# Grove_-_Mini_Track_ball_v1_0.net
KiCad netlist of a schematic drawn in EAGLE
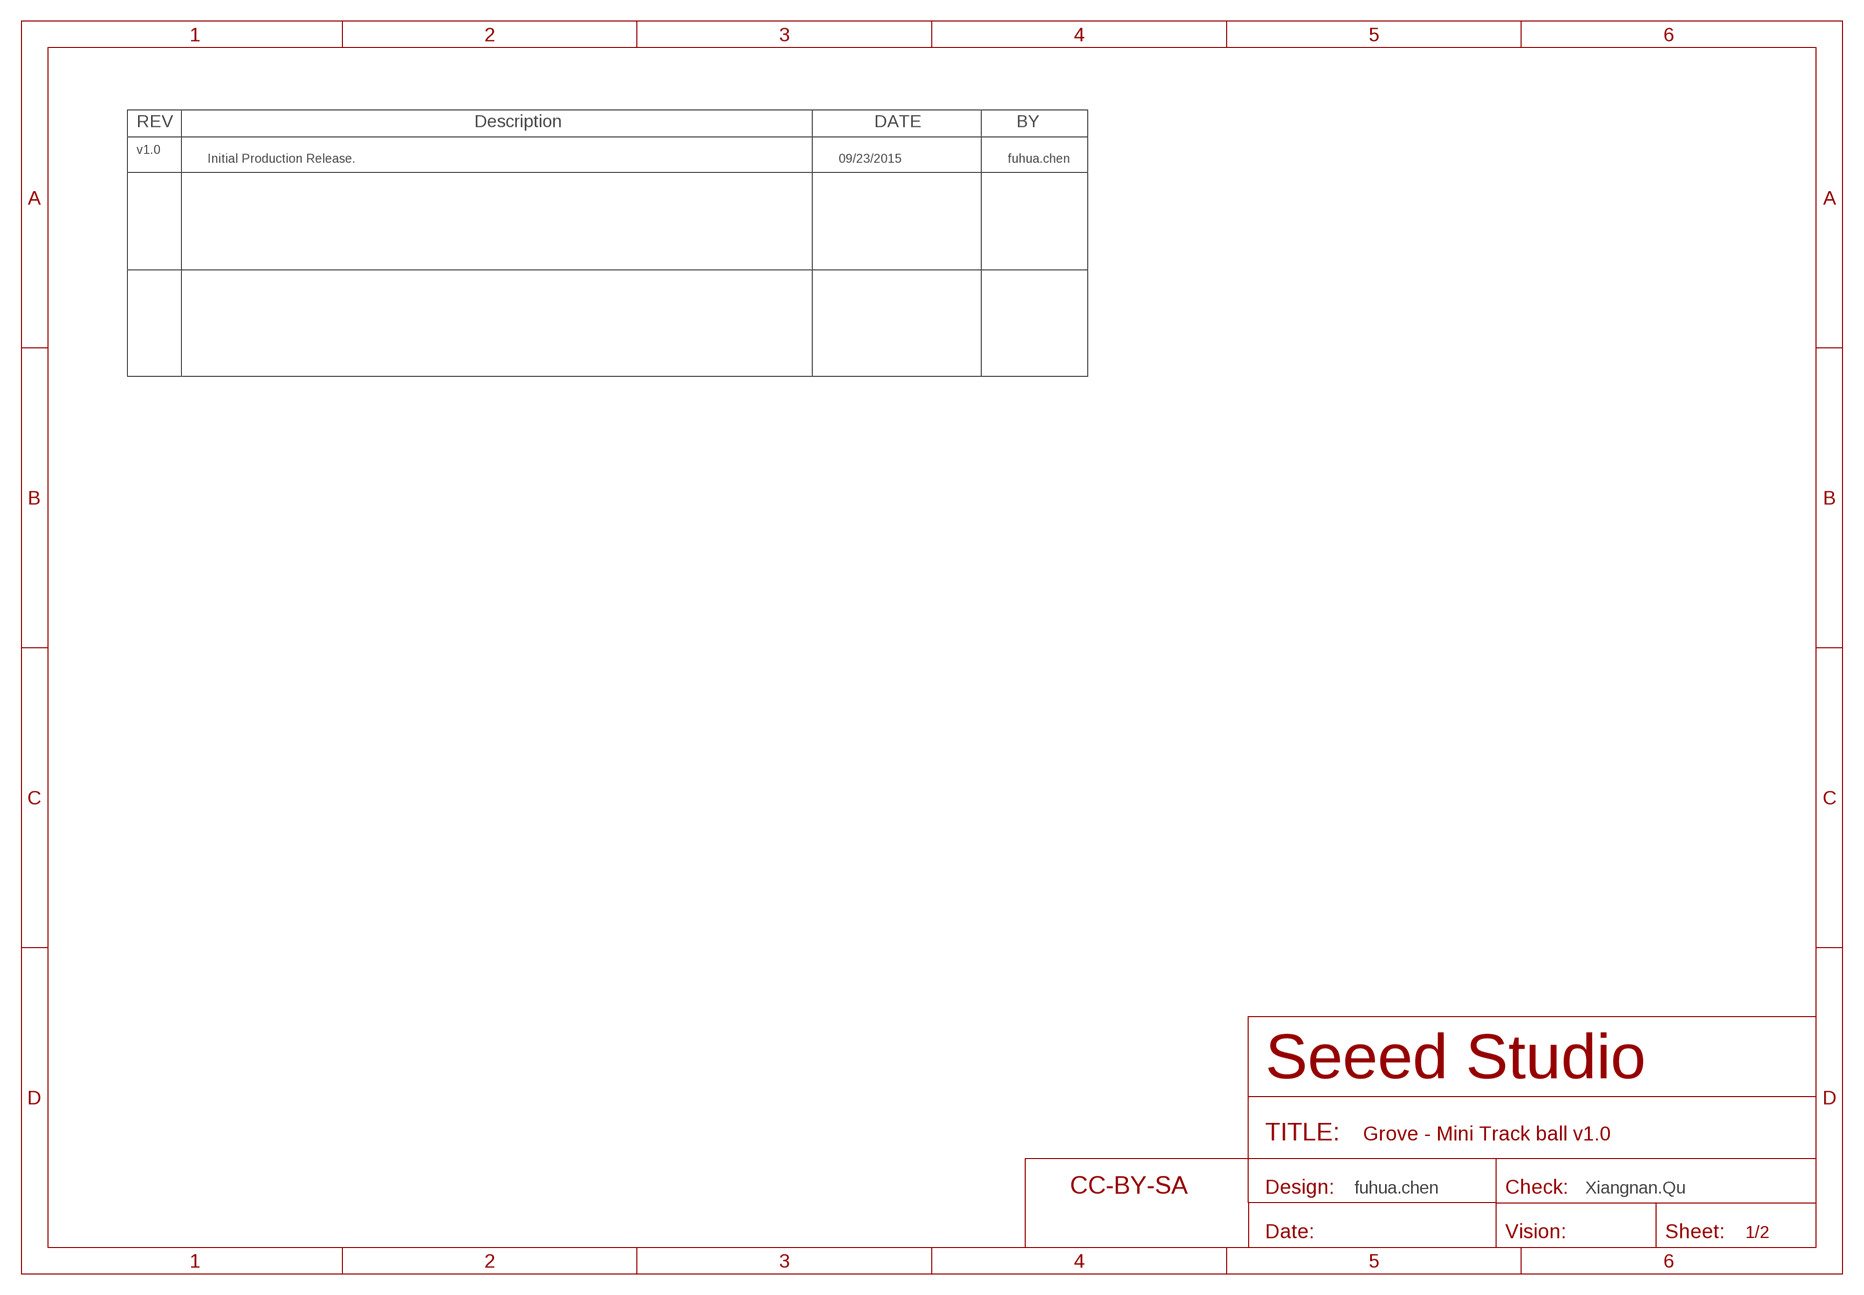
[diagram p0: schematic, sheet 1]
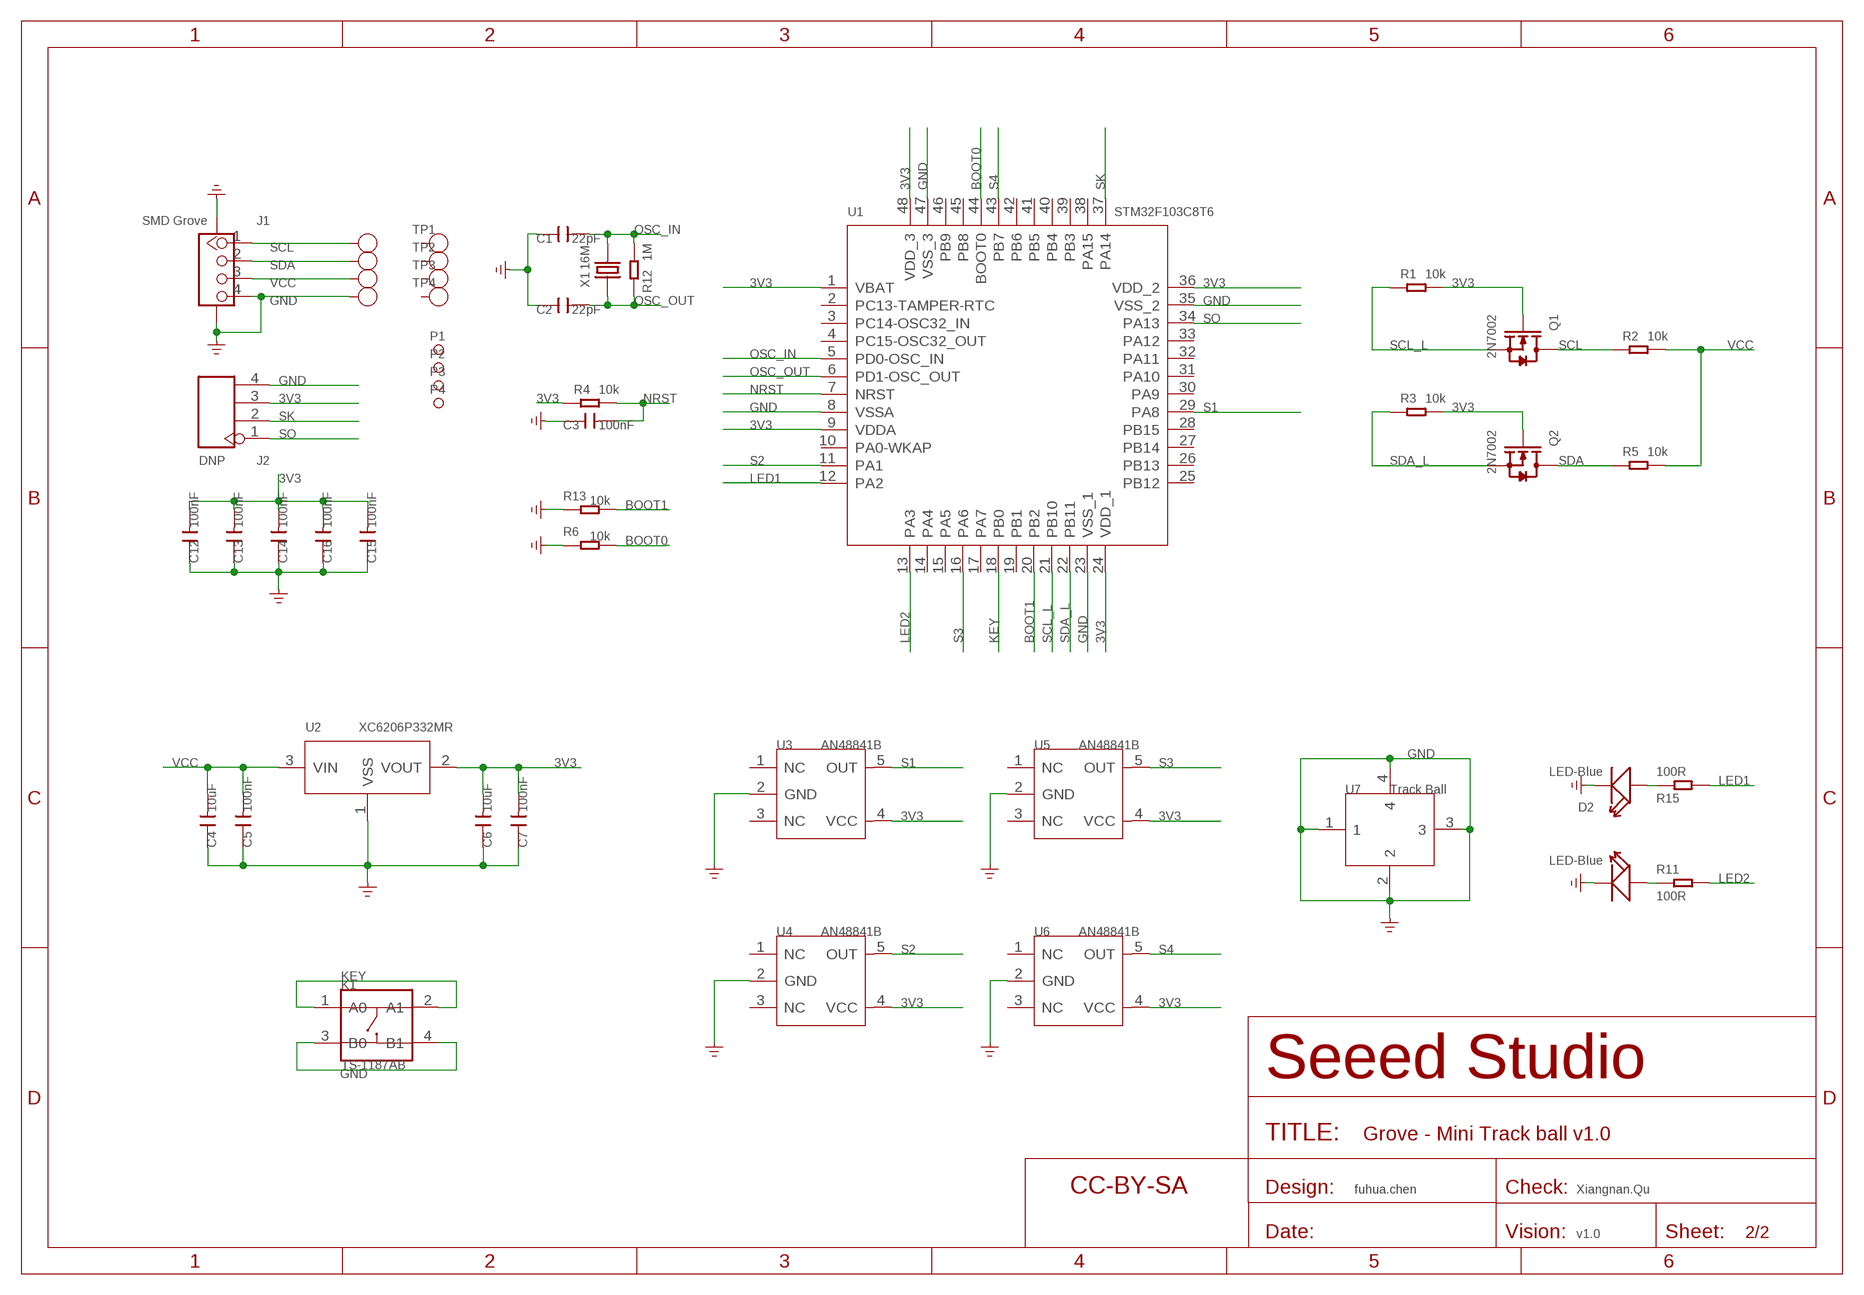
[diagram p1: schematic, sheet 2]

(export (version "E")
  (design (tool "Eeschema 10.0.6"))
  (components
    (comp (ref "C1")
      (value "22pF")
      (footprint "eagle-import:C0402")
      (libsource (lib "eagle-import") (part "CAP-0402"))
    )
    (comp (ref "C2")
      (value "22pF")
      (footprint "eagle-import:C0402")
      (libsource (lib "eagle-import") (part "CAP-0402"))
    )
    (comp (ref "C3")
      (value "100nF")
      (footprint "eagle-import:C0402")
      (libsource (lib "eagle-import") (part "CAP-0402"))
    )
    (comp (ref "C4")
      (value "10uF")
      (footprint "eagle-import:C0402")
      (libsource (lib "eagle-import") (part "CAP-0402"))
    )
    (comp (ref "C5")
      (value "100nF")
      (footprint "eagle-import:C0402")
      (libsource (lib "eagle-import") (part "CAP-0402"))
    )
    (comp (ref "C6")
      (value "10uF")
      (footprint "eagle-import:C0402")
      (libsource (lib "eagle-import") (part "CAP-0402"))
    )
    (comp (ref "C7")
      (value "100nF")
      (footprint "eagle-import:C0402")
      (libsource (lib "eagle-import") (part "CAP-0402"))
    )
    (comp (ref "C12")
      (value "100nF")
      (footprint "eagle-import:C0402")
      (libsource (lib "eagle-import") (part "CAP-0402"))
    )
    (comp (ref "C13")
      (value "100nF")
      (footprint "eagle-import:C0402")
      (libsource (lib "eagle-import") (part "CAP-0402"))
    )
    (comp (ref "C14")
      (value "100nF")
      (footprint "eagle-import:C0402")
      (libsource (lib "eagle-import") (part "CAP-0402"))
    )
    (comp (ref "C15")
      (value "100nF")
      (footprint "eagle-import:C0402")
      (libsource (lib "eagle-import") (part "CAP-0402"))
    )
    (comp (ref "C16")
      (value "100nF")
      (footprint "eagle-import:C0402")
      (libsource (lib "eagle-import") (part "CAP-0402"))
    )
    (comp (ref "D1")
      (value "LED-Blue")
      (footprint "eagle-import:LED-0402")
      (libsource (lib "eagle-import") (part "LED'0402'"))
    )
    (comp (ref "D2")
      (value "LED-Blue")
      (footprint "eagle-import:LED-0402")
      (libsource (lib "eagle-import") (part "LED'0402'"))
    )
    (comp (ref "FR")
      (value "SEEEDSTUDIO-OPEN-SCH-FRAME")
      (footprint "eagle-import:SEEEDSTUDIO-PCB-FRAME")
      (libsource (lib "eagle-import") (part "SEEEDSTUDIO-OPEN-SCH-FRAME"))
    )
    (comp (ref "GND")
      (value "GND")
      (footprint "eagle-import:TP-D45MIL")
      (fields (field (name "PARTNO") "DNP"))
      (libsource (lib "eagle-import") (part "TEST-POINT'4545'"))
    )
    (comp (ref "J1")
      (value "SMD Grove")
      (footprint "eagle-import:HW4-SMD-2.0-90D")
      (libsource (lib "eagle-import") (part "GROVE-CONNECTOR-SMD'90D'"))
    )
    (comp (ref "J2")
      (value "DNP")
      (footprint "eagle-import:H4-2.54")
      (libsource (lib "eagle-import") (part "HEADER-4P-65/35MIL"))
    )
    (comp (ref "K1")
      (value "TS-1187AB")
      (footprint "eagle-import:SW4-4.5X4.5X0.5MM")
      (libsource (lib "eagle-import") (part "BUTTON-4P-4.5X4.5"))
    )
    (comp (ref "P1")
      (value "MARK-1.0'ANNULAR'")
      (footprint "eagle-import:ROUND-MARK-1.0")
      (fields (field (name "PARTNO") "DNP"))
      (libsource (lib "eagle-import") (part "MARK-1.0'ANNULAR'"))
    )
    (comp (ref "P2")
      (value "MARK-1.0'ANNULAR'")
      (footprint "eagle-import:ROUND-MARK-1.0")
      (fields (field (name "PARTNO") "DNP"))
      (libsource (lib "eagle-import") (part "MARK-1.0'ANNULAR'"))
    )
    (comp (ref "P3")
      (value "MARK-1.0'ANNULAR'")
      (footprint "eagle-import:ROUND-MARK-1.0")
      (fields (field (name "PARTNO") "DNP"))
      (libsource (lib "eagle-import") (part "MARK-1.0'ANNULAR'"))
    )
    (comp (ref "P4")
      (value "MARK-1.0'ANNULAR'")
      (footprint "eagle-import:ROUND-MARK-1.0")
      (fields (field (name "PARTNO") "DNP"))
      (libsource (lib "eagle-import") (part "MARK-1.0'ANNULAR'"))
    )
    (comp (ref "Q1")
      (value "2N7002")
      (footprint "eagle-import:SOT-23")
      (libsource (lib "eagle-import") (part "MOSFET-N'SOT23'"))
    )
    (comp (ref "Q2")
      (value "2N7002")
      (footprint "eagle-import:SOT-23")
      (libsource (lib "eagle-import") (part "MOSFET-N'SOT23'"))
    )
    (comp (ref "R1")
      (value "10k")
      (footprint "eagle-import:R0402")
      (libsource (lib "eagle-import") (part "RES-0402"))
    )
    (comp (ref "R2")
      (value "10k")
      (footprint "eagle-import:R0402")
      (libsource (lib "eagle-import") (part "RES-0402"))
    )
    (comp (ref "R3")
      (value "10k")
      (footprint "eagle-import:R0402")
      (libsource (lib "eagle-import") (part "RES-0402"))
    )
    (comp (ref "R4")
      (value "10k")
      (footprint "eagle-import:R0402")
      (libsource (lib "eagle-import") (part "RES-0402"))
    )
    (comp (ref "R5")
      (value "10k")
      (footprint "eagle-import:R0402")
      (libsource (lib "eagle-import") (part "RES-0402"))
    )
    (comp (ref "R6")
      (value "10k")
      (footprint "eagle-import:R0402")
      (libsource (lib "eagle-import") (part "RES-0402"))
    )
    (comp (ref "R11")
      (value "100R")
      (footprint "eagle-import:R0402")
      (libsource (lib "eagle-import") (part "RES-0402"))
    )
    (comp (ref "R12")
      (value "1M")
      (footprint "eagle-import:R0402")
      (libsource (lib "eagle-import") (part "RES-0402"))
    )
    (comp (ref "R13")
      (value "10k")
      (footprint "eagle-import:R0402")
      (libsource (lib "eagle-import") (part "RES-0402"))
    )
    (comp (ref "R15")
      (value "100R")
      (footprint "eagle-import:R0402")
      (libsource (lib "eagle-import") (part "RES-0402"))
    )
    (comp (ref "SCL")
      (value "SCL")
      (footprint "eagle-import:TP-D45MIL")
      (fields (field (name "PARTNO") "DNP"))
      (libsource (lib "eagle-import") (part "TEST-POINT'4545'"))
    )
    (comp (ref "SDA")
      (value "SDA")
      (footprint "eagle-import:TP-D45MIL")
      (fields (field (name "PARTNO") "DNP"))
      (libsource (lib "eagle-import") (part "TEST-POINT'4545'"))
    )
    (comp (ref "TP1")
      (value "TEST-POINT'4545'")
      (footprint "eagle-import:TP-D45MIL")
      (fields (field (name "PARTNO") "DNP"))
      (libsource (lib "eagle-import") (part "TEST-POINT'4545'"))
    )
    (comp (ref "TP2")
      (value "TEST-POINT'4545'")
      (footprint "eagle-import:TP-D45MIL")
      (fields (field (name "PARTNO") "DNP"))
      (libsource (lib "eagle-import") (part "TEST-POINT'4545'"))
    )
    (comp (ref "TP3")
      (value "TEST-POINT'4545'")
      (footprint "eagle-import:TP-D45MIL")
      (fields (field (name "PARTNO") "DNP"))
      (libsource (lib "eagle-import") (part "TEST-POINT'4545'"))
    )
    (comp (ref "TP4")
      (value "TEST-POINT'4545'")
      (footprint "eagle-import:TP-D45MIL")
      (fields (field (name "PARTNO") "DNP"))
      (libsource (lib "eagle-import") (part "TEST-POINT'4545'"))
    )
    (comp (ref "U1")
      (value "STM32F103C8T6")
      (footprint "eagle-import:LQFP48")
      (libsource (lib "eagle-import") (part "MCU-STM32F103CBT6"))
    )
    (comp (ref "U2")
      (value "XC6206P332MR")
      (footprint "eagle-import:SOT-23")
      (libsource (lib "eagle-import") (part "PMIC-XC6206PMR"))
    )
    (comp (ref "U3")
      (value "AN48841B")
      (footprint "eagle-import:SMINI-5DE")
      (libsource (lib "eagle-import") (part "SENSOR-AN48841B"))
    )
    (comp (ref "U4")
      (value "AN48841B")
      (footprint "eagle-import:SMINI-5DE")
      (libsource (lib "eagle-import") (part "SENSOR-AN48841B"))
    )
    (comp (ref "U5")
      (value "AN48841B")
      (footprint "eagle-import:SMINI-5DE")
      (libsource (lib "eagle-import") (part "SENSOR-AN48841B"))
    )
    (comp (ref "U6")
      (value "AN48841B")
      (footprint "eagle-import:SMINI-5DE")
      (libsource (lib "eagle-import") (part "SENSOR-AN48841B"))
    )
    (comp (ref "U7")
      (value "Track Ball")
      (footprint "eagle-import:BALL4P-9.1X9.1X6.04MM")
      (libsource (lib "eagle-import") (part "TRACK-BALL"))
    )
    (comp (ref "VCC")
      (value "VCC")
      (footprint "eagle-import:TP-D45MIL")
      (fields (field (name "PARTNO") "DNP"))
      (libsource (lib "eagle-import") (part "TEST-POINT'4545'"))
    )
    (comp (ref "X1")
      (value "16M")
      (footprint "eagle-import:X4-SMD-3.2X2.5X0.7MM")
      (libsource (lib "eagle-import") (part "CRYSTAL-2P'3225'"))
    )
    (comp (ref "U$13")
      (value "SEEEDSTUDIO-OPEN-SCH-FRAME")
      (footprint "eagle-import:SEEEDSTUDIO-PCB-FRAME")
      (libsource (lib "eagle-import") (part "SEEEDSTUDIO-OPEN-SCH-FRAME"))
    )
  )
  (nets
    (net (code "1") (name "3V3") (class "Default")
      (node (ref "C12") (pin "2") (pinfunction "2_2") (pintype "passive"))
      (node (ref "C13") (pin "2") (pinfunction "2_2") (pintype "passive"))
      (node (ref "C14") (pin "2") (pinfunction "2_2") (pintype "passive"))
      (node (ref "C15") (pin "2") (pinfunction "2_2") (pintype "passive"))
      (node (ref "C16") (pin "2") (pinfunction "2_2") (pintype "passive"))
      (node (ref "C6") (pin "2") (pinfunction "2_2") (pintype "passive"))
      (node (ref "C7") (pin "2") (pinfunction "2_2") (pintype "passive"))
      (node (ref "J2") (pin "3") (pinfunction "P$3_3") (pintype "bidirectional"))
      (node (ref "Q1") (pin "1") (pinfunction "G_1") (pintype "passive"))
      (node (ref "Q2") (pin "1") (pinfunction "G_1") (pintype "passive"))
      (node (ref "R1") (pin "2") (pinfunction "2_2") (pintype "passive"))
      (node (ref "R3") (pin "2") (pinfunction "2_2") (pintype "passive"))
      (node (ref "R4") (pin "1") (pinfunction "1_1") (pintype "passive"))
      (node (ref "U1") (pin "1") (pinfunction "VBAT_1") (pintype "bidirectional"))
      (node (ref "U1") (pin "24") (pinfunction "VDD_1_24") (pintype "bidirectional"))
      (node (ref "U1") (pin "36") (pinfunction "VDD_2_36") (pintype "bidirectional"))
      (node (ref "U1") (pin "48") (pinfunction "VDD_3_48") (pintype "bidirectional"))
      (node (ref "U1") (pin "9") (pinfunction "VDDA_9") (pintype "bidirectional"))
      (node (ref "U2") (pin "2") (pinfunction "VOUT_2") (pintype "bidirectional"))
      (node (ref "U3") (pin "4") (pinfunction "VCC_4") (pintype "bidirectional"))
      (node (ref "U4") (pin "4") (pinfunction "VCC_4") (pintype "bidirectional"))
      (node (ref "U5") (pin "4") (pinfunction "VCC_4") (pintype "bidirectional"))
      (node (ref "U6") (pin "4") (pinfunction "VCC_4") (pintype "bidirectional"))
    )
    (net (code "2") (name "BOOT0") (class "Default")
      (node (ref "R6") (pin "2") (pinfunction "2_2") (pintype "passive"))
      (node (ref "U1") (pin "44") (pinfunction "BOOT0_44") (pintype "bidirectional"))
    )
    (net (code "3") (name "BOOT1") (class "Default")
      (node (ref "R13") (pin "2") (pinfunction "2_2") (pintype "passive"))
      (node (ref "U1") (pin "20") (pinfunction "PB2_20") (pintype "bidirectional"))
    )
    (net (code "4") (name "GND") (class "Default")
      (node (ref "C1") (pin "1") (pinfunction "1_1") (pintype "passive"))
      (node (ref "C12") (pin "1") (pinfunction "1_1") (pintype "passive"))
      (node (ref "C13") (pin "1") (pinfunction "1_1") (pintype "passive"))
      (node (ref "C14") (pin "1") (pinfunction "1_1") (pintype "passive"))
      (node (ref "C15") (pin "1") (pinfunction "1_1") (pintype "passive"))
      (node (ref "C16") (pin "1") (pinfunction "1_1") (pintype "passive"))
      (node (ref "C2") (pin "1") (pinfunction "1_1") (pintype "passive"))
      (node (ref "C3") (pin "1") (pinfunction "1_1") (pintype "passive"))
      (node (ref "C4") (pin "1") (pinfunction "1_1") (pintype "passive"))
      (node (ref "C5") (pin "1") (pinfunction "1_1") (pintype "passive"))
      (node (ref "C6") (pin "1") (pinfunction "1_1") (pintype "passive"))
      (node (ref "C7") (pin "1") (pinfunction "1_1") (pintype "passive"))
      (node (ref "D1") (pin "-") (pinfunction "-_-") (pintype "passive"))
      (node (ref "D2") (pin "-") (pinfunction "-_-") (pintype "passive"))
      (node (ref "GND") (pin "T") (pinfunction "T_T") (pintype "bidirectional"))
      (node (ref "J1") (pin "4") (pinfunction "4_4") (pintype "bidirectional"))
      (node (ref "J1") (pin "SS1") (pinfunction "SS1_SS1") (pintype "bidirectional"))
      (node (ref "J1") (pin "SS2") (pinfunction "SS2_SS2") (pintype "bidirectional"))
      (node (ref "J2") (pin "4") (pinfunction "P$4_4") (pintype "bidirectional"))
      (node (ref "K1") (pin "3") (pinfunction "B0_3") (pintype "bidirectional"))
      (node (ref "K1") (pin "4") (pinfunction "B1_4") (pintype "bidirectional"))
      (node (ref "R13") (pin "1") (pinfunction "1_1") (pintype "passive"))
      (node (ref "R6") (pin "1") (pinfunction "1_1") (pintype "passive"))
      (node (ref "U1") (pin "23") (pinfunction "VSS_1_23") (pintype "bidirectional"))
      (node (ref "U1") (pin "35") (pinfunction "VSS_2_35") (pintype "bidirectional"))
      (node (ref "U1") (pin "47") (pinfunction "VSS_3_47") (pintype "bidirectional"))
      (node (ref "U1") (pin "8") (pinfunction "VSSA_8") (pintype "bidirectional"))
      (node (ref "U2") (pin "1") (pinfunction "VSS_1") (pintype "bidirectional"))
      (node (ref "U3") (pin "2") (pinfunction "GND_2") (pintype "bidirectional"))
      (node (ref "U4") (pin "2") (pinfunction "GND_2") (pintype "bidirectional"))
      (node (ref "U5") (pin "2") (pinfunction "GND_2") (pintype "bidirectional"))
      (node (ref "U6") (pin "2") (pinfunction "GND_2") (pintype "bidirectional"))
      (node (ref "U7") (pin "1") (pinfunction "1_1") (pintype "bidirectional"))
      (node (ref "U7") (pin "2") (pinfunction "2_2") (pintype "bidirectional"))
      (node (ref "U7") (pin "3") (pinfunction "3_3") (pintype "bidirectional"))
      (node (ref "U7") (pin "4") (pinfunction "4_4") (pintype "bidirectional"))
    )
    (net (code "5") (name "KEY") (class "Default")
      (node (ref "K1") (pin "1") (pinfunction "A0_1") (pintype "bidirectional"))
      (node (ref "K1") (pin "2") (pinfunction "A1_2") (pintype "bidirectional"))
      (node (ref "U1") (pin "18") (pinfunction "PB0_18") (pintype "bidirectional"))
    )
    (net (code "6") (name "LED1") (class "Default")
      (node (ref "R15") (pin "2") (pinfunction "2_2") (pintype "passive"))
      (node (ref "U1") (pin "12") (pinfunction "PA2_12") (pintype "bidirectional"))
    )
    (net (code "7") (name "LED2") (class "Default")
      (node (ref "R11") (pin "2") (pinfunction "2_2") (pintype "passive"))
      (node (ref "U1") (pin "13") (pinfunction "PA3_13") (pintype "bidirectional"))
    )
    (net (code "8") (name "NRST") (class "Default")
      (node (ref "C3") (pin "2") (pinfunction "2_2") (pintype "passive"))
      (node (ref "R4") (pin "2") (pinfunction "2_2") (pintype "passive"))
      (node (ref "U1") (pin "7") (pinfunction "NRST_7") (pintype "bidirectional"))
    )
    (net (code "9") (name "Net-(D1-Pad+)") (class "Default")
      (node (ref "D1") (pin "+") (pinfunction "+_+") (pintype "passive"))
      (node (ref "R11") (pin "1") (pinfunction "1_1") (pintype "passive"))
    )
    (net (code "10") (name "Net-(D2-Pad+)") (class "Default")
      (node (ref "D2") (pin "+") (pinfunction "+_+") (pintype "passive"))
      (node (ref "R15") (pin "1") (pinfunction "1_1") (pintype "passive"))
    )
    (net (code "11") (name "OSC_IN") (class "Default")
      (node (ref "C1") (pin "2") (pinfunction "2_2") (pintype "passive"))
      (node (ref "R12") (pin "2") (pinfunction "2_2") (pintype "passive"))
      (node (ref "U1") (pin "5") (pinfunction "PD0-OSC_IN_5") (pintype "bidirectional"))
      (node (ref "X1") (pin "4") (pinfunction "2_4") (pintype "passive"))
    )
    (net (code "12") (name "OSC_OUT") (class "Default")
      (node (ref "C2") (pin "2") (pinfunction "2_2") (pintype "passive"))
      (node (ref "R12") (pin "1") (pinfunction "1_1") (pintype "passive"))
      (node (ref "U1") (pin "6") (pinfunction "PD1-OSC_OUT_6") (pintype "bidirectional"))
      (node (ref "X1") (pin "2") (pinfunction "1_2") (pintype "passive"))
    )
    (net (code "13") (name "S1") (class "Default")
      (node (ref "U1") (pin "29") (pinfunction "PA8_29") (pintype "bidirectional"))
      (node (ref "U3") (pin "5") (pinfunction "OUT_5") (pintype "bidirectional"))
    )
    (net (code "14") (name "S2") (class "Default")
      (node (ref "U1") (pin "11") (pinfunction "PA1_11") (pintype "bidirectional"))
      (node (ref "U4") (pin "5") (pinfunction "OUT_5") (pintype "bidirectional"))
    )
    (net (code "15") (name "S3") (class "Default")
      (node (ref "U1") (pin "16") (pinfunction "PA6_16") (pintype "bidirectional"))
      (node (ref "U5") (pin "5") (pinfunction "OUT_5") (pintype "bidirectional"))
    )
    (net (code "16") (name "S4") (class "Default")
      (node (ref "U1") (pin "43") (pinfunction "PB7_43") (pintype "bidirectional"))
      (node (ref "U6") (pin "5") (pinfunction "OUT_5") (pintype "bidirectional"))
    )
    (net (code "17") (name "SCL") (class "Default")
      (node (ref "J1") (pin "1") (pinfunction "1_1") (pintype "bidirectional"))
      (node (ref "Q1") (pin "3") (pinfunction "D_3") (pintype "passive"))
      (node (ref "R2") (pin "1") (pinfunction "1_1") (pintype "passive"))
      (node (ref "SCL") (pin "T") (pinfunction "T_T") (pintype "bidirectional"))
    )
    (net (code "18") (name "SCL_L") (class "Default")
      (node (ref "Q1") (pin "2") (pinfunction "S_2") (pintype "passive"))
      (node (ref "R1") (pin "1") (pinfunction "1_1") (pintype "passive"))
      (node (ref "U1") (pin "21") (pinfunction "PB10_21") (pintype "bidirectional"))
    )
    (net (code "19") (name "SDA") (class "Default")
      (node (ref "J1") (pin "2") (pinfunction "2_2") (pintype "bidirectional"))
      (node (ref "Q2") (pin "3") (pinfunction "D_3") (pintype "passive"))
      (node (ref "R5") (pin "1") (pinfunction "1_1") (pintype "passive"))
      (node (ref "SDA") (pin "T") (pinfunction "T_T") (pintype "bidirectional"))
    )
    (net (code "20") (name "SDA_L") (class "Default")
      (node (ref "Q2") (pin "2") (pinfunction "S_2") (pintype "passive"))
      (node (ref "R3") (pin "1") (pinfunction "1_1") (pintype "passive"))
      (node (ref "U1") (pin "22") (pinfunction "PB11_22") (pintype "bidirectional"))
    )
    (net (code "21") (name "SK") (class "Default")
      (node (ref "J2") (pin "2") (pinfunction "P$2_2") (pintype "bidirectional"))
      (node (ref "U1") (pin "37") (pinfunction "PA14_37") (pintype "bidirectional"))
    )
    (net (code "22") (name "SO") (class "Default")
      (node (ref "J2") (pin "1") (pinfunction "P$1_1") (pintype "bidirectional"))
      (node (ref "U1") (pin "34") (pinfunction "PA13_34") (pintype "bidirectional"))
    )
    (net (code "23") (name "VCC") (class "Default")
      (node (ref "C4") (pin "2") (pinfunction "2_2") (pintype "passive"))
      (node (ref "C5") (pin "2") (pinfunction "2_2") (pintype "passive"))
      (node (ref "J1") (pin "3") (pinfunction "3_3") (pintype "bidirectional"))
      (node (ref "R2") (pin "2") (pinfunction "2_2") (pintype "passive"))
      (node (ref "R5") (pin "2") (pinfunction "2_2") (pintype "passive"))
      (node (ref "U2") (pin "3") (pinfunction "VIN_3") (pintype "bidirectional"))
      (node (ref "VCC") (pin "T") (pinfunction "T_T") (pintype "bidirectional"))
    )
    (net (code "24") (name "unconnected-(TP1-PadT)") (class "Default")
      (node (ref "TP1") (pin "T") (pinfunction "T_T") (pintype "bidirectional"))
    )
    (net (code "25") (name "unconnected-(TP2-PadT)") (class "Default")
      (node (ref "TP2") (pin "T") (pinfunction "T_T") (pintype "bidirectional"))
    )
    (net (code "26") (name "unconnected-(TP3-PadT)") (class "Default")
      (node (ref "TP3") (pin "T") (pinfunction "T_T") (pintype "bidirectional"))
    )
    (net (code "27") (name "unconnected-(TP4-PadT)") (class "Default")
      (node (ref "TP4") (pin "T") (pinfunction "T_T") (pintype "bidirectional"))
    )
    (net (code "28") (name "unconnected-(U1-PA0-WKAP-Pad10)") (class "Default")
      (node (ref "U1") (pin "10") (pinfunction "PA0-WKAP_10") (pintype "bidirectional"))
    )
    (net (code "29") (name "unconnected-(U1-PA4-Pad14)") (class "Default")
      (node (ref "U1") (pin "14") (pinfunction "PA4_14") (pintype "bidirectional"))
    )
    (net (code "30") (name "unconnected-(U1-PA5-Pad15)") (class "Default")
      (node (ref "U1") (pin "15") (pinfunction "PA5_15") (pintype "bidirectional"))
    )
    (net (code "31") (name "unconnected-(U1-PA7-Pad17)") (class "Default")
      (node (ref "U1") (pin "17") (pinfunction "PA7_17") (pintype "bidirectional"))
    )
    (net (code "32") (name "unconnected-(U1-PA9-Pad30)") (class "Default")
      (node (ref "U1") (pin "30") (pinfunction "PA9_30") (pintype "bidirectional"))
    )
    (net (code "33") (name "unconnected-(U1-PA10-Pad31)") (class "Default")
      (node (ref "U1") (pin "31") (pinfunction "PA10_31") (pintype "bidirectional"))
    )
    (net (code "34") (name "unconnected-(U1-PA11-Pad32)") (class "Default")
      (node (ref "U1") (pin "32") (pinfunction "PA11_32") (pintype "bidirectional"))
    )
    (net (code "35") (name "unconnected-(U1-PA12-Pad33)") (class "Default")
      (node (ref "U1") (pin "33") (pinfunction "PA12_33") (pintype "bidirectional"))
    )
    (net (code "36") (name "unconnected-(U1-PA15-Pad38)") (class "Default")
      (node (ref "U1") (pin "38") (pinfunction "PA15_38") (pintype "bidirectional"))
    )
    (net (code "37") (name "unconnected-(U1-PB1-Pad19)") (class "Default")
      (node (ref "U1") (pin "19") (pinfunction "PB1_19") (pintype "bidirectional"))
    )
    (net (code "38") (name "unconnected-(U1-PB3-Pad39)") (class "Default")
      (node (ref "U1") (pin "39") (pinfunction "PB3_39") (pintype "bidirectional"))
    )
    (net (code "39") (name "unconnected-(U1-PB4-Pad40)") (class "Default")
      (node (ref "U1") (pin "40") (pinfunction "PB4_40") (pintype "bidirectional"))
    )
    (net (code "40") (name "unconnected-(U1-PB5-Pad41)") (class "Default")
      (node (ref "U1") (pin "41") (pinfunction "PB5_41") (pintype "bidirectional"))
    )
    (net (code "41") (name "unconnected-(U1-PB6-Pad42)") (class "Default")
      (node (ref "U1") (pin "42") (pinfunction "PB6_42") (pintype "bidirectional"))
    )
    (net (code "42") (name "unconnected-(U1-PB8-Pad45)") (class "Default")
      (node (ref "U1") (pin "45") (pinfunction "PB8_45") (pintype "bidirectional"))
    )
    (net (code "43") (name "unconnected-(U1-PB9-Pad46)") (class "Default")
      (node (ref "U1") (pin "46") (pinfunction "PB9_46") (pintype "bidirectional"))
    )
    (net (code "44") (name "unconnected-(U1-PB12-Pad25)") (class "Default")
      (node (ref "U1") (pin "25") (pinfunction "PB12_25") (pintype "bidirectional"))
    )
    (net (code "45") (name "unconnected-(U1-PB13-Pad26)") (class "Default")
      (node (ref "U1") (pin "26") (pinfunction "PB13_26") (pintype "bidirectional"))
    )
    (net (code "46") (name "unconnected-(U1-PB14-Pad27)") (class "Default")
      (node (ref "U1") (pin "27") (pinfunction "PB14_27") (pintype "bidirectional"))
    )
    (net (code "47") (name "unconnected-(U1-PB15-Pad28)") (class "Default")
      (node (ref "U1") (pin "28") (pinfunction "PB15_28") (pintype "bidirectional"))
    )
    (net (code "48") (name "unconnected-(U1-PC13-TAMPER-RTC-Pad2)") (class "Default")
      (node (ref "U1") (pin "2") (pinfunction "PC13-TAMPER-RTC_2") (pintype "bidirectional"))
    )
    (net (code "49") (name "unconnected-(U1-PC14-OSC32_IN-Pad3)") (class "Default")
      (node (ref "U1") (pin "3") (pinfunction "PC14-OSC32_IN_3") (pintype "bidirectional"))
    )
    (net (code "50") (name "unconnected-(U1-PC15-OSC32_OUT-Pad4)") (class "Default")
      (node (ref "U1") (pin "4") (pinfunction "PC15-OSC32_OUT_4") (pintype "bidirectional"))
    )
    (net (code "51") (name "unconnected-(U3-NC-Pad1)") (class "Default")
      (node (ref "U3") (pin "1") (pinfunction "NC_1") (pintype "bidirectional"))
    )
    (net (code "52") (name "unconnected-(U3-NC-Pad3)") (class "Default")
      (node (ref "U3") (pin "3") (pinfunction "NC_3") (pintype "bidirectional"))
    )
    (net (code "53") (name "unconnected-(U4-NC-Pad1)") (class "Default")
      (node (ref "U4") (pin "1") (pinfunction "NC_1") (pintype "bidirectional"))
    )
    (net (code "54") (name "unconnected-(U4-NC-Pad3)") (class "Default")
      (node (ref "U4") (pin "3") (pinfunction "NC_3") (pintype "bidirectional"))
    )
    (net (code "55") (name "unconnected-(U5-NC-Pad1)") (class "Default")
      (node (ref "U5") (pin "1") (pinfunction "NC_1") (pintype "bidirectional"))
    )
    (net (code "56") (name "unconnected-(U5-NC-Pad3)") (class "Default")
      (node (ref "U5") (pin "3") (pinfunction "NC_3") (pintype "bidirectional"))
    )
    (net (code "57") (name "unconnected-(U6-NC-Pad1)") (class "Default")
      (node (ref "U6") (pin "1") (pinfunction "NC_1") (pintype "bidirectional"))
    )
    (net (code "58") (name "unconnected-(U6-NC-Pad3)") (class "Default")
      (node (ref "U6") (pin "3") (pinfunction "NC_3") (pintype "bidirectional"))
    )
  )
)
